# 1-Schematic_LaserGame_plastron_v1.net
KiCad netlist of a schematic drawn in EasyEDA
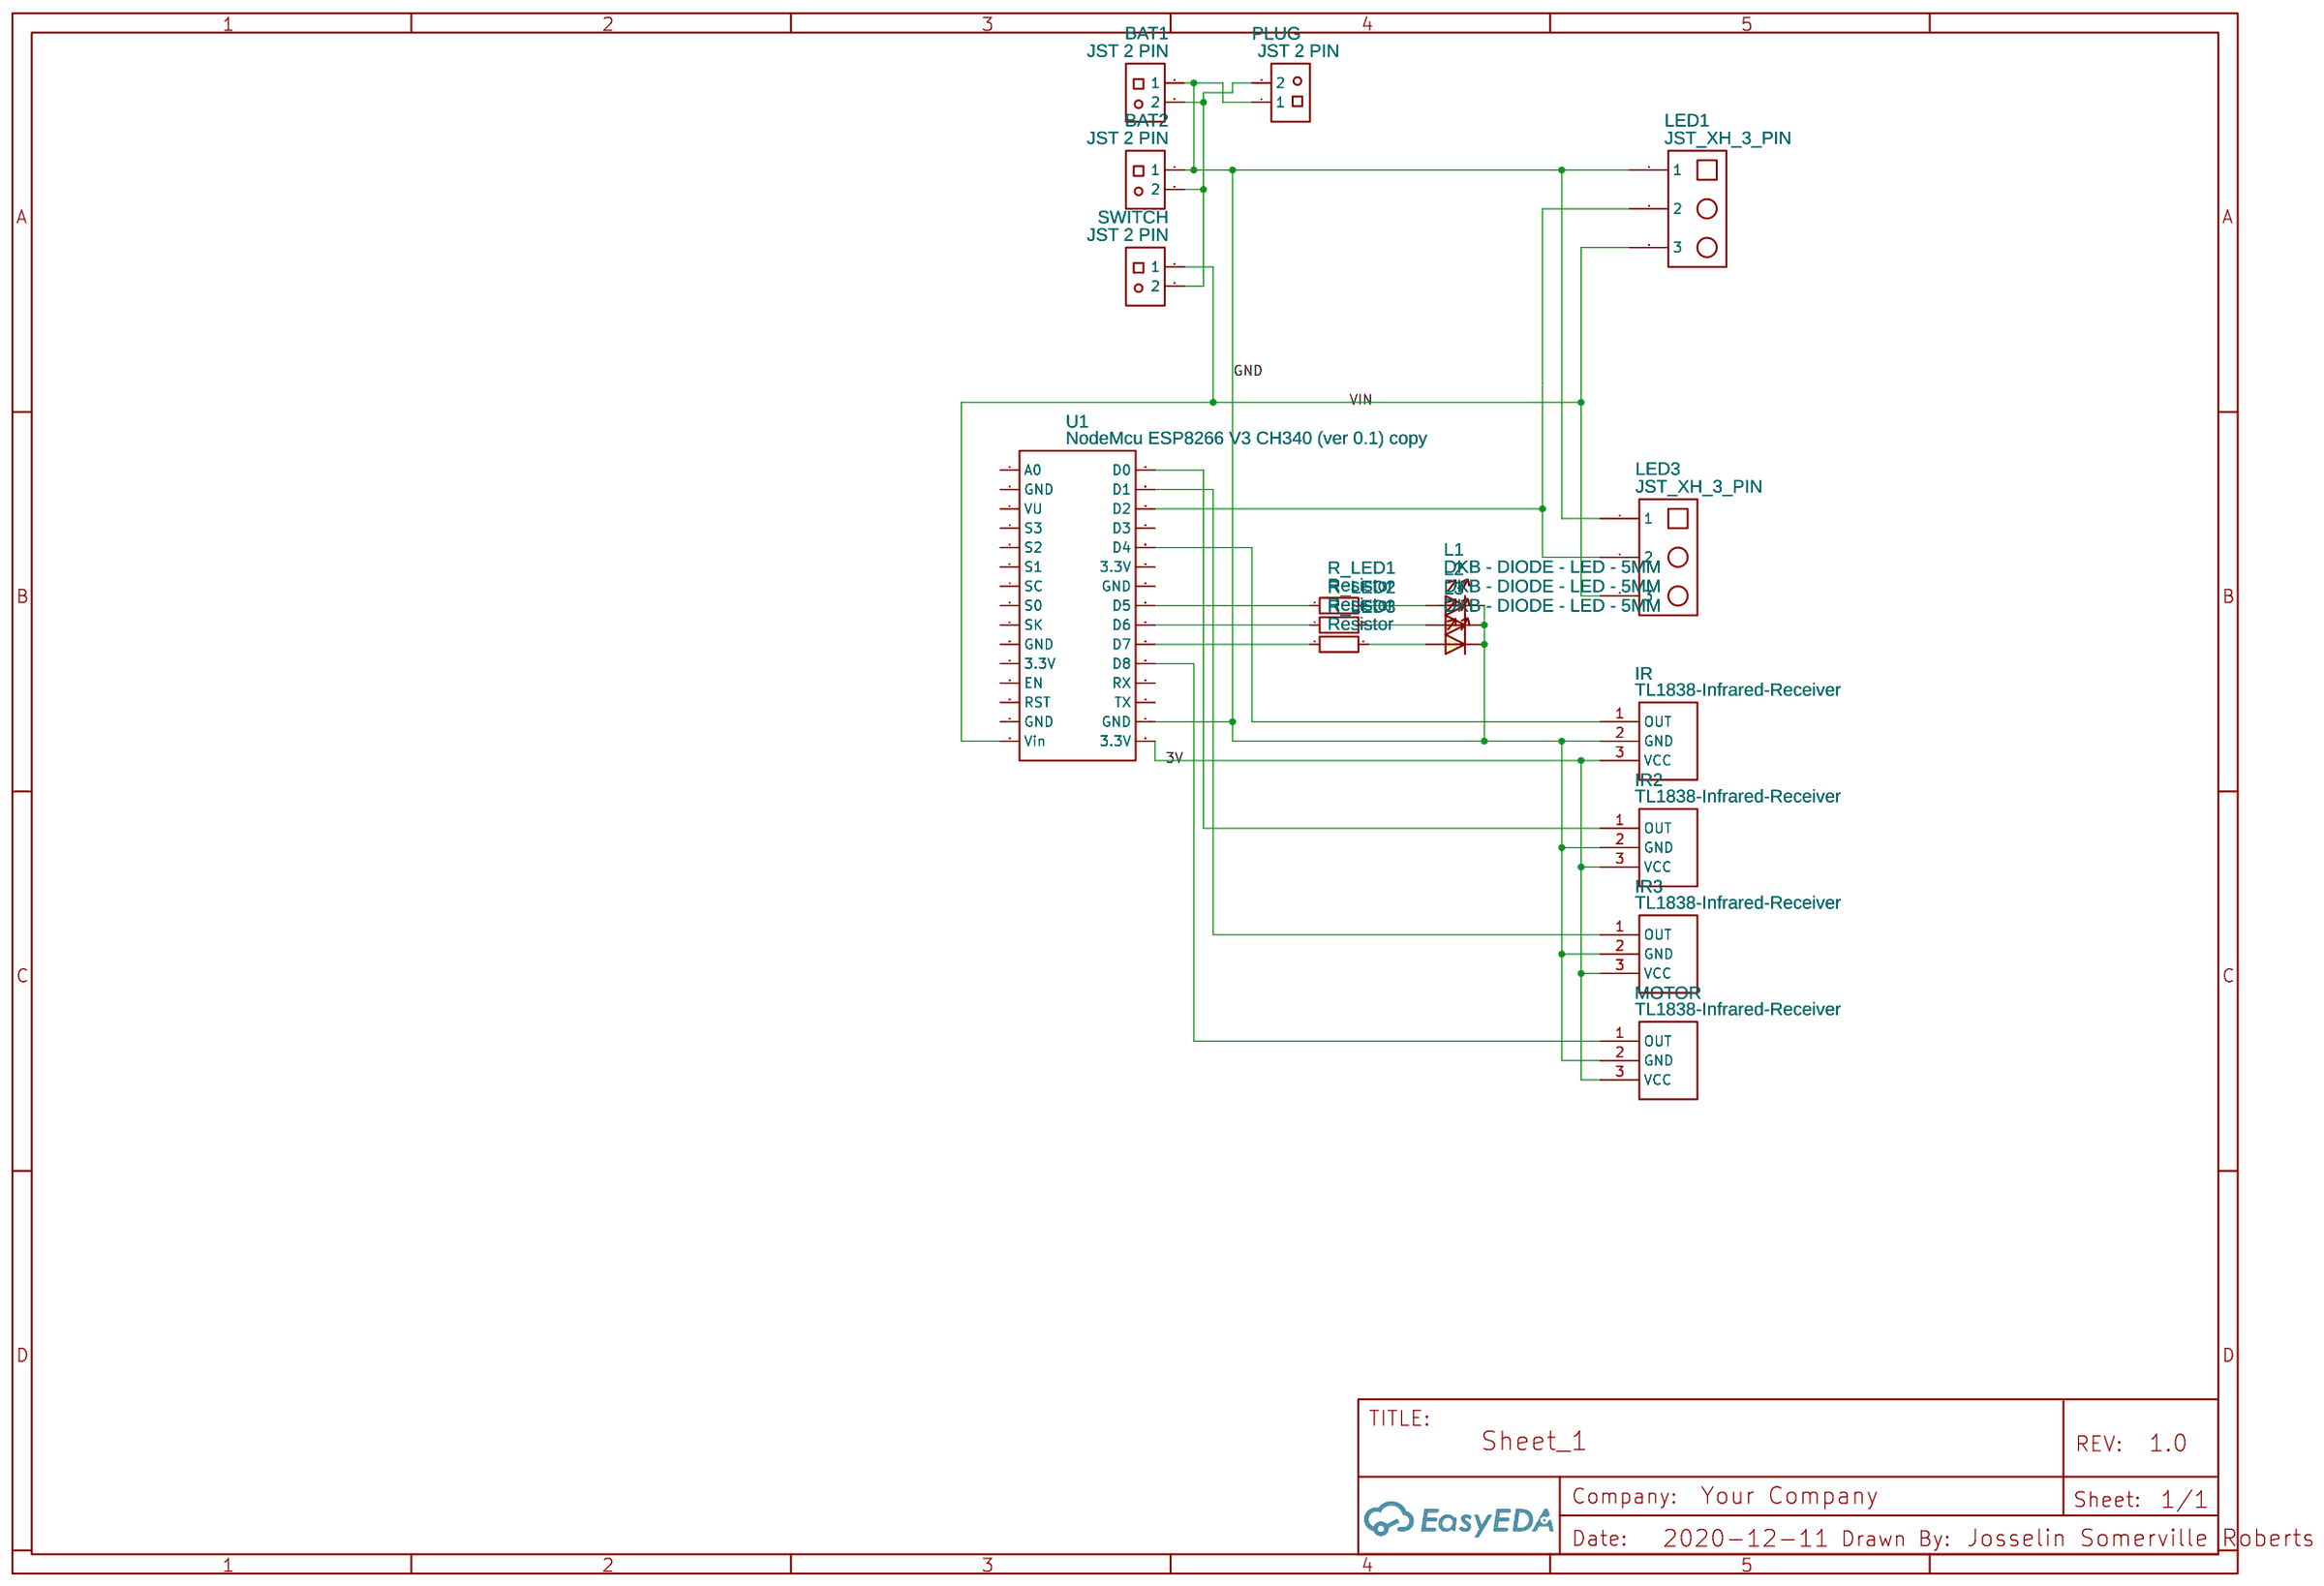
[diagram p0: schematic sheet]

(export (version "E")
  (design (tool "Eeschema 10.0.6"))
  (components
    (comp (ref "BAT1")
      (value "JST 2 PIN")
      (fields (field (name "BOM_Manufacturer Part") "JST_XH CONNECTOR"))
      (libsource (lib "") (part "JST 2 PIN_1"))
    )
    (comp (ref "BAT2")
      (value "JST 2 PIN")
      (fields (field (name "BOM_Manufacturer Part") "JST_XH CONNECTOR"))
      (libsource (lib "") (part "JST 2 PIN_1"))
    )
    (comp (ref "IR")
      (value "TL1838-Infrared-Receiver")
      (fields (field (name "BOM_Manufacturer Part") "TL1838"))
      (libsource (lib "") (part "TL1838-Infrared-Receiver"))
    )
    (comp (ref "IR2")
      (value "TL1838-Infrared-Receiver")
      (fields (field (name "BOM_Manufacturer Part") "TL1838"))
      (libsource (lib "") (part "TL1838-Infrared-Receiver"))
    )
    (comp (ref "IR3")
      (value "TL1838-Infrared-Receiver")
      (fields (field (name "BOM_Manufacturer Part") "TL1838"))
      (libsource (lib "") (part "TL1838-Infrared-Receiver"))
    )
    (comp (ref "L1")
      (value "DKB - DIODE - LED - 5MM")
      (fields (field (name "BOM_Manufacturer Part") "5mm LED"))
      (libsource (lib "") (part "DKB - DIODE - LED - 5MM"))
    )
    (comp (ref "L2")
      (value "DKB - DIODE - LED - 5MM")
      (fields (field (name "BOM_Manufacturer Part") "5mm LED"))
      (libsource (lib "") (part "DKB - DIODE - LED - 5MM"))
    )
    (comp (ref "L3")
      (value "DKB - DIODE - LED - 5MM")
      (fields (field (name "BOM_Manufacturer Part") "5mm LED"))
      (libsource (lib "") (part "DKB - DIODE - LED - 5MM"))
    )
    (comp (ref "LED1")
      (value "JST_XH_3_PIN")
      (fields (field (name "BOM_Manufacturer Part") "JST AMERICAN SALES"))
      (libsource (lib "") (part "JST_XH_3_PIN"))
    )
    (comp (ref "LED3")
      (value "JST_XH_3_PIN")
      (fields (field (name "BOM_Manufacturer Part") "JST AMERICAN SALES"))
      (libsource (lib "") (part "JST_XH_3_PIN"))
    )
    (comp (ref "MOTOR")
      (value "TL1838-Infrared-Receiver")
      (fields (field (name "BOM_Manufacturer Part") "TL1838"))
      (libsource (lib "") (part "TL1838-Infrared-Receiver_1"))
    )
    (comp (ref "PLUG")
      (value "JST 2 PIN")
      (fields (field (name "BOM_Manufacturer Part") "JST_XH CONNECTOR"))
      (libsource (lib "") (part "JST 2 PIN_2"))
    )
    (comp (ref "R_LED1") (value "Resistor") (libsource (lib "") (part "Resistor")))
    (comp (ref "R_LED2") (value "Resistor") (libsource (lib "") (part "Resistor")))
    (comp (ref "R_LED3") (value "Resistor") (libsource (lib "") (part "Resistor")))
    (comp (ref "SWITCH")
      (value "JST 2 PIN")
      (fields (field (name "BOM_Manufacturer Part") "JST_XH CONNECTOR"))
      (libsource (lib "") (part "JST 2 PIN"))
    )
    (comp (ref "U1")
      (value "NodeMcu ESP8266 V3 CH340 (ver 0.1) copy")
      (fields (field (name "BOM_Manufacturer Part") "CH340 NodeMcu V3"))
      (libsource (lib "") (part "NodeMcu ESP8266 V3 CH340 (ver 0.1) copy"))
    )
  )
  (nets
    (net (code "1") (name "/3V") (class "Default")
      (node (ref "IR") (pin "3") (pinfunction "VCC_3") (pintype "passive"))
      (node (ref "IR2") (pin "3") (pinfunction "VCC_3") (pintype "passive"))
      (node (ref "IR3") (pin "3") (pinfunction "VCC_3") (pintype "passive"))
      (node (ref "MOTOR") (pin "3") (pinfunction "VCC_3") (pintype "passive"))
      (node (ref "U1") (pin "16") (pinfunction "3.3V_16") (pintype "unspecified"))
    )
    (net (code "2") (name "/GND") (class "Default")
      (node (ref "BAT1") (pin "1") (pinfunction "1_1") (pintype "unspecified"))
      (node (ref "BAT2") (pin "1") (pinfunction "1_1") (pintype "unspecified"))
      (node (ref "IR") (pin "2") (pinfunction "GND_2") (pintype "passive"))
      (node (ref "IR2") (pin "2") (pinfunction "GND_2") (pintype "passive"))
      (node (ref "IR3") (pin "2") (pinfunction "GND_2") (pintype "passive"))
      (node (ref "L1") (pin "2") (pinfunction "2_2") (pintype "unspecified"))
      (node (ref "L2") (pin "2") (pinfunction "2_2") (pintype "unspecified"))
      (node (ref "L3") (pin "2") (pinfunction "2_2") (pintype "unspecified"))
      (node (ref "LED1") (pin "1") (pinfunction "1_1") (pintype "unspecified"))
      (node (ref "LED3") (pin "1") (pinfunction "1_1") (pintype "unspecified"))
      (node (ref "MOTOR") (pin "2") (pinfunction "GND_2") (pintype "passive"))
      (node (ref "PLUG") (pin "1") (pinfunction "1_1") (pintype "unspecified"))
      (node (ref "U1") (pin "17") (pinfunction "GND_17") (pintype "unspecified"))
    )
    (net (code "3") (name "/VIN") (class "Default")
      (node (ref "LED1") (pin "3") (pinfunction "3_3") (pintype "unspecified"))
      (node (ref "LED3") (pin "3") (pinfunction "3_3") (pintype "unspecified"))
      (node (ref "SWITCH") (pin "1") (pinfunction "1_1") (pintype "unspecified"))
      (node (ref "U1") (pin "15") (pinfunction "Vin_15") (pintype "unspecified"))
    )
    (net (code "4") (name "Net-(BAT1-Pad2)") (class "Default")
      (node (ref "BAT1") (pin "2") (pinfunction "2_2") (pintype "unspecified"))
      (node (ref "BAT2") (pin "2") (pinfunction "2_2") (pintype "unspecified"))
      (node (ref "PLUG") (pin "2") (pinfunction "2_2") (pintype "unspecified"))
      (node (ref "SWITCH") (pin "2") (pinfunction "2_2") (pintype "unspecified"))
    )
    (net (code "5") (name "Net-(IR-OUT)") (class "Default")
      (node (ref "IR") (pin "1") (pinfunction "OUT_1") (pintype "output"))
      (node (ref "U1") (pin "26") (pinfunction "D4_26") (pintype "unspecified"))
    )
    (net (code "6") (name "Net-(IR2-OUT)") (class "Default")
      (node (ref "IR2") (pin "1") (pinfunction "OUT_1") (pintype "output"))
      (node (ref "U1") (pin "30") (pinfunction "D0_30") (pintype "unspecified"))
    )
    (net (code "7") (name "Net-(IR3-OUT)") (class "Default")
      (node (ref "IR3") (pin "1") (pinfunction "OUT_1") (pintype "output"))
      (node (ref "U1") (pin "29") (pinfunction "D1_29") (pintype "unspecified"))
    )
    (net (code "8") (name "Net-(L1-Pad1)") (class "Default")
      (node (ref "L1") (pin "1") (pinfunction "1_1") (pintype "unspecified"))
      (node (ref "R_LED1") (pin "1") (pintype "unspecified"))
    )
    (net (code "9") (name "Net-(L2-Pad1)") (class "Default")
      (node (ref "L2") (pin "1") (pinfunction "1_1") (pintype "unspecified"))
      (node (ref "R_LED2") (pin "1") (pintype "unspecified"))
    )
    (net (code "10") (name "Net-(L3-Pad1)") (class "Default")
      (node (ref "L3") (pin "1") (pinfunction "1_1") (pintype "unspecified"))
      (node (ref "R_LED3") (pin "1") (pintype "unspecified"))
    )
    (net (code "11") (name "Net-(MOTOR-OUT)") (class "Default")
      (node (ref "MOTOR") (pin "1") (pinfunction "OUT_1") (pintype "output"))
      (node (ref "U1") (pin "20") (pinfunction "D8_20") (pintype "unspecified"))
    )
    (net (code "12") (name "Net-(U1-D2)") (class "Default")
      (node (ref "LED1") (pin "2") (pinfunction "2_2") (pintype "unspecified"))
      (node (ref "LED3") (pin "2") (pinfunction "2_2") (pintype "unspecified"))
      (node (ref "U1") (pin "28") (pinfunction "D2_28") (pintype "unspecified"))
    )
    (net (code "13") (name "Net-(U1-D5)") (class "Default")
      (node (ref "R_LED1") (pin "2") (pintype "unspecified"))
      (node (ref "U1") (pin "23") (pinfunction "D5_23") (pintype "unspecified"))
    )
    (net (code "14") (name "Net-(U1-D6)") (class "Default")
      (node (ref "R_LED2") (pin "2") (pintype "unspecified"))
      (node (ref "U1") (pin "22") (pinfunction "D6_22") (pintype "unspecified"))
    )
    (net (code "15") (name "Net-(U1-D7)") (class "Default")
      (node (ref "R_LED3") (pin "2") (pintype "unspecified"))
      (node (ref "U1") (pin "21") (pinfunction "D7_21") (pintype "unspecified"))
    )
    (net (code "16") (name "unconnected-(U1-3.3V-Pad11)") (class "Default")
      (node (ref "U1") (pin "11") (pinfunction "3.3V_11") (pintype "unspecified"))
    )
    (net (code "17") (name "unconnected-(U1-3.3V-Pad25)") (class "Default")
      (node (ref "U1") (pin "25") (pinfunction "3.3V_25") (pintype "unspecified"))
    )
    (net (code "18") (name "unconnected-(U1-A0-Pad1)") (class "Default")
      (node (ref "U1") (pin "1") (pinfunction "A0_1") (pintype "unspecified"))
    )
    (net (code "19") (name "unconnected-(U1-D3-Pad27)") (class "Default")
      (node (ref "U1") (pin "27") (pinfunction "D3_27") (pintype "unspecified"))
    )
    (net (code "20") (name "unconnected-(U1-EN-Pad12)") (class "Default")
      (node (ref "U1") (pin "12") (pinfunction "EN_12") (pintype "unspecified"))
    )
    (net (code "21") (name "unconnected-(U1-GND-Pad2)") (class "Default")
      (node (ref "U1") (pin "2") (pinfunction "GND_2") (pintype "unspecified"))
    )
    (net (code "22") (name "unconnected-(U1-GND-Pad10)") (class "Default")
      (node (ref "U1") (pin "10") (pinfunction "GND_10") (pintype "unspecified"))
    )
    (net (code "23") (name "unconnected-(U1-GND-Pad14)") (class "Default")
      (node (ref "U1") (pin "14") (pinfunction "GND_14") (pintype "unspecified"))
    )
    (net (code "24") (name "unconnected-(U1-GND-Pad24)") (class "Default")
      (node (ref "U1") (pin "24") (pinfunction "GND_24") (pintype "unspecified"))
    )
    (net (code "25") (name "unconnected-(U1-RST-Pad13)") (class "Default")
      (node (ref "U1") (pin "13") (pinfunction "RST_13") (pintype "unspecified"))
    )
    (net (code "26") (name "unconnected-(U1-RX-Pad19)") (class "Default")
      (node (ref "U1") (pin "19") (pinfunction "RX_19") (pintype "unspecified"))
    )
    (net (code "27") (name "unconnected-(U1-S0-Pad8)") (class "Default")
      (node (ref "U1") (pin "8") (pinfunction "S0_8") (pintype "unspecified"))
    )
    (net (code "28") (name "unconnected-(U1-S1-Pad6)") (class "Default")
      (node (ref "U1") (pin "6") (pinfunction "S1_6") (pintype "unspecified"))
    )
    (net (code "29") (name "unconnected-(U1-S2-Pad5)") (class "Default")
      (node (ref "U1") (pin "5") (pinfunction "S2_5") (pintype "unspecified"))
    )
    (net (code "30") (name "unconnected-(U1-S3-Pad4)") (class "Default")
      (node (ref "U1") (pin "4") (pinfunction "S3_4") (pintype "unspecified"))
    )
    (net (code "31") (name "unconnected-(U1-SC-Pad7)") (class "Default")
      (node (ref "U1") (pin "7") (pinfunction "SC_7") (pintype "unspecified"))
    )
    (net (code "32") (name "unconnected-(U1-SK-Pad9)") (class "Default")
      (node (ref "U1") (pin "9") (pinfunction "SK_9") (pintype "unspecified"))
    )
    (net (code "33") (name "unconnected-(U1-TX-Pad18)") (class "Default")
      (node (ref "U1") (pin "18") (pinfunction "TX_18") (pintype "unspecified"))
    )
    (net (code "34") (name "unconnected-(U1-VU-Pad3)") (class "Default")
      (node (ref "U1") (pin "3") (pinfunction "VU_3") (pintype "unspecified"))
    )
  )
)
